# EC_meter.net
KiCad netlist of a schematic drawn in Altium Designer
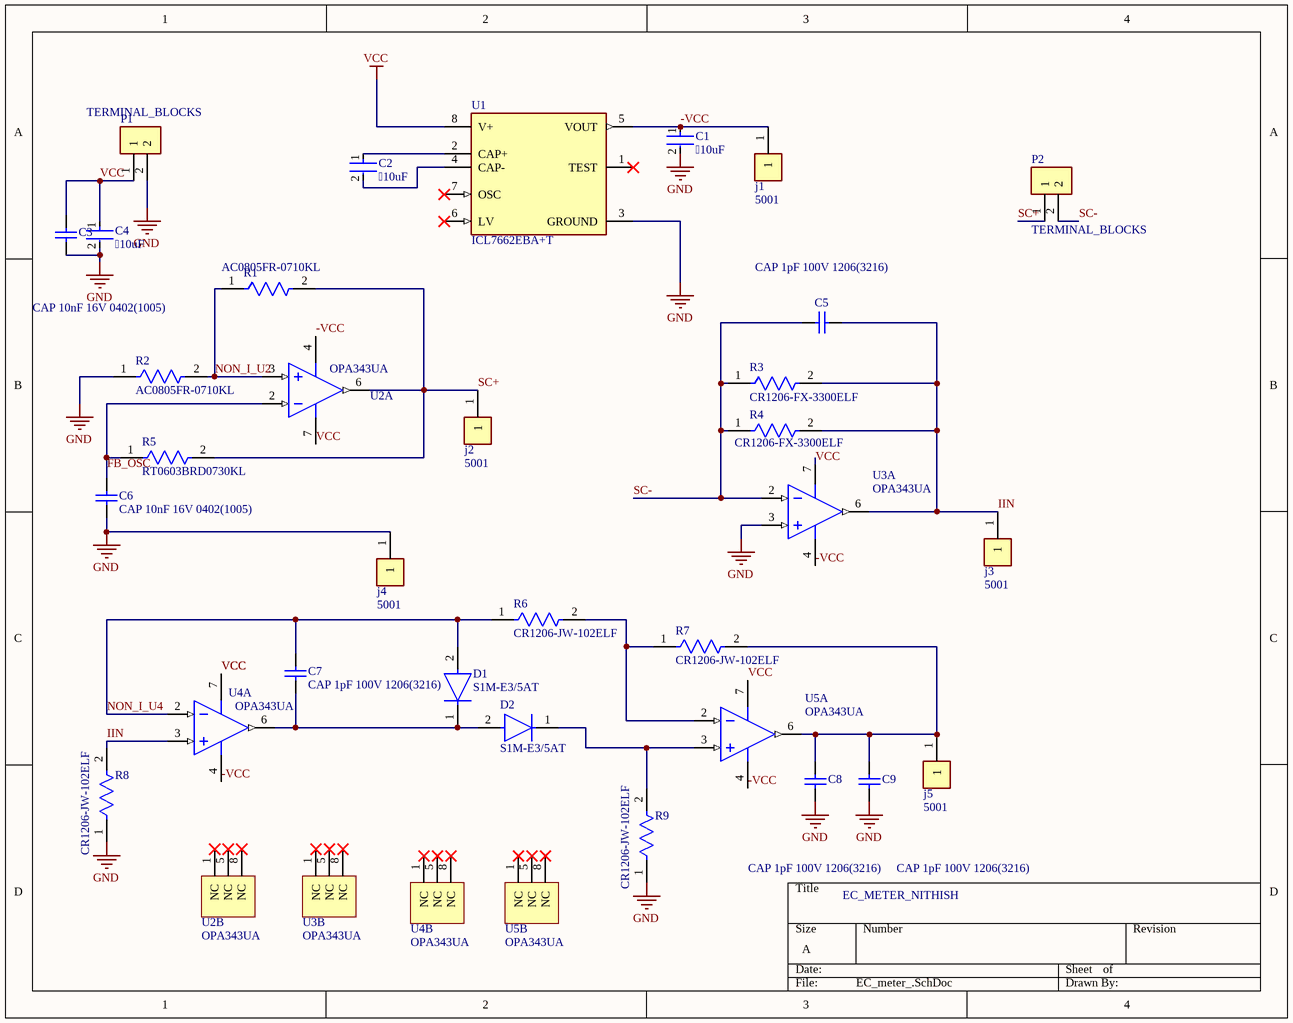
[diagram p0: EC_meter_.SchDoc]

(export (version "E")
  (design (tool "Eeschema 10.0.6"))
  (components
    (comp (ref "C1")
      (value "10uF")
      (footprint "FP-GRM31-0_2-MFG")
      (description "CAP CER 10UF 50V X5R 1206")
      (fields
        (field (name "OCTOPART") "https://octopart.com/grm31cr61h106ka12l-murata-18903335")
        (field (name "TOLERANCE") "10%")
      )
      (libsource (lib "Altium Content Vault") (part "11868f565c42a9108669ba33697ecf6"))
    )
    (comp (ref "C2")
      (value "10uF")
      (footprint "FP-GRM31-0_2-MFG")
      (description "CAP CER 10UF 50V X5R 1206")
      (fields
        (field (name "OCTOPART") "https://octopart.com/grm31cr61h106ka12l-murata-18903335")
        (field (name "TOLERANCE") "10%")
      )
      (libsource (lib "Altium Content Vault") (part "11868f565c42a9108669ba33697ecf6"))
    )
    (comp (ref "C3")
      (value "CAP 10nF 16V 0402(1005)")
      (footprint "CAPC0402(1005)60_M")
      (description "CAP 10nF 16V -20% to +80% 0402 (1005 Metric) Thickness 0.6mm SMD")
      (fields (field (name "TOLERANCE") "-20% to +80%"))
      (libsource (lib "Altium Content Vault") (part "CAP"))
    )
    (comp (ref "C4")
      (value "10uF")
      (footprint "FP-GRM31-0_2-MFG")
      (description "CAP CER 10UF 50V X5R 1206")
      (fields
        (field (name "OCTOPART") "https://octopart.com/grm31cr61h106ka12l-murata-18903335")
        (field (name "TOLERANCE") "10%")
      )
      (libsource (lib "Altium Content Vault") (part "11868f565c42a9108669ba33697ecf6"))
    )
    (comp (ref "C5")
      (value "CAP 1pF 100V 1206(3216)")
      (footprint "CAPC1206(3216)170_N")
      (description "CAP 1pF 100V ±0.25pF 1206 (3216 Metric) Thickness 1.7mm SMD")
      (fields (field (name "TOLERANCE") "Â±0.25pF"))
      (libsource (lib "Altium Content Vault") (part "CAP"))
    )
    (comp (ref "C6")
      (value "CAP 10nF 16V 0402(1005)")
      (footprint "CAPC0402(1005)60_M")
      (description "CAP 10nF 16V -20% to +80% 0402 (1005 Metric) Thickness 0.6mm SMD")
      (fields (field (name "TOLERANCE") "-20% to +80%"))
      (libsource (lib "Altium Content Vault") (part "CAP"))
    )
    (comp (ref "C7")
      (value "CAP 1pF 100V 1206(3216)")
      (footprint "CAPC1206(3216)170_N")
      (description "CAP 1pF 100V ±0.25pF 1206 (3216 Metric) Thickness 1.7mm SMD")
      (fields (field (name "TOLERANCE") "Â±0.25pF"))
      (libsource (lib "Altium Content Vault") (part "CAP"))
    )
    (comp (ref "C8")
      (value "CAP 1pF 100V 1206(3216)")
      (footprint "CAPC1206(3216)170_N")
      (description "CAP 1pF 100V ±0.25pF 1206 (3216 Metric) Thickness 1.7mm SMD")
      (fields (field (name "TOLERANCE") "Â±0.25pF"))
      (libsource (lib "Altium Content Vault") (part "CAP"))
    )
    (comp (ref "C9")
      (value "CAP 1pF 100V 1206(3216)")
      (footprint "CAPC1206(3216)170_N")
      (description "CAP 1pF 100V ±0.25pF 1206 (3216 Metric) Thickness 1.7mm SMD")
      (fields (field (name "TOLERANCE") "Â±0.25pF"))
      (libsource (lib "Altium Content Vault") (part "CAP"))
    )
    (comp (ref "D1")
      (value "S1M-E3/5AT")
      (footprint "FP-95400-MFG")
      (description "DIODE GEN PURP 1KV 1A DO214AC")
      (fields
        (field (name "OCTOPART") "https://octopart.com/s1m-e3%2F5at-vishay-42334588")
        (field (name "MANUFACTURER") "Vishay")
      )
      (libsource (lib "Altium Content Vault") (part "d7152d700b627762746794eb795d46e"))
    )
    (comp (ref "D2")
      (value "S1M-E3/5AT")
      (footprint "FP-95400-MFG")
      (description "DIODE GEN PURP 1KV 1A DO214AC")
      (fields
        (field (name "OCTOPART") "https://octopart.com/s1m-e3%2F5at-vishay-42334588")
        (field (name "MANUFACTURER") "Vishay")
      )
      (libsource (lib "Altium Content Vault") (part "d7152d700b627762746794eb795d46e"))
    )
    (comp (ref "j1")
      (value "5001")
      (footprint "FP-5001-MFG")
      (description "PC TEST POINT MINIATURE BLACK")
      (libsource (lib "Altium Content Vault") (part "1e4615820a309e3ce90f9e6d957b7fa"))
    )
    (comp (ref "j2")
      (value "5001")
      (footprint "FP-5001-MFG")
      (description "PC TEST POINT MINIATURE BLACK")
      (libsource (lib "Altium Content Vault") (part "1e4615820a309e3ce90f9e6d957b7fa"))
    )
    (comp (ref "j3")
      (value "5001")
      (footprint "FP-5001-MFG")
      (description "PC TEST POINT MINIATURE BLACK")
      (libsource (lib "Altium Content Vault") (part "1e4615820a309e3ce90f9e6d957b7fa"))
    )
    (comp (ref "j4")
      (value "5001")
      (footprint "FP-5001-MFG")
      (description "PC TEST POINT MINIATURE BLACK")
      (libsource (lib "Altium Content Vault") (part "1e4615820a309e3ce90f9e6d957b7fa"))
    )
    (comp (ref "j5")
      (value "5001")
      (footprint "FP-5001-MFG")
      (description "PC TEST POINT MINIATURE BLACK")
      (libsource (lib "Altium Content Vault") (part "1e4615820a309e3ce90f9e6d957b7fa"))
    )
    (comp (ref "P1")
      (value "TERMINAL_BLOCKS")
      (footprint "PCBComponent_1 - duplicate")
      (libsource (lib "EC_meter") (part "TERMINAL_BLOCKS"))
    )
    (comp (ref "P2")
      (value "TERMINAL_BLOCKS")
      (footprint "PCBComponent_1 - duplicate")
      (libsource (lib "EC_meter") (part "TERMINAL_BLOCKS"))
    )
    (comp (ref "R1")
      (value "AC0805FR-0710KL")
      (footprint "FP-AC0805-MFG")
      (description "RES SMD 10K OHM 1% 1/8W 0805")
      (fields
        (field (name "OCTOPART") "https://octopart.com/ac0805fr-0710kl-yageo-21711112")
        (field (name "MANUFACTURER") "Yageo")
      )
      (libsource (lib "Altium Content Vault") (part "1029c3af85768c4190bb7ad29bc67b5"))
    )
    (comp (ref "R2")
      (value "AC0805FR-0710KL")
      (footprint "FP-AC0805-MFG")
      (description "RES SMD 10K OHM 1% 1/8W 0805")
      (fields
        (field (name "OCTOPART") "https://octopart.com/ac0805fr-0710kl-yageo-21711112")
        (field (name "MANUFACTURER") "Yageo")
      )
      (libsource (lib "Altium Content Vault") (part "1029c3af85768c4190bb7ad29bc67b5"))
    )
    (comp (ref "R3")
      (value "CR1206-FX-3300ELF")
      (footprint "FP-CR1206-MFG")
      (description "Thick Film Chip Resistors 1206 330Ω 0.25W 1% 100ppm/°C")
      (fields (field (name "TOLERANCE") "1%"))
      (libsource (lib "Altium Content Vault") (part "1029c3af85768c4190bb7ad29bc67b5"))
    )
    (comp (ref "R4")
      (value "CR1206-FX-3300ELF")
      (footprint "FP-CR1206-MFG")
      (description "Thick Film Chip Resistors 1206 330Ω 0.25W 1% 100ppm/°C")
      (fields (field (name "TOLERANCE") "1%"))
      (libsource (lib "Altium Content Vault") (part "1029c3af85768c4190bb7ad29bc67b5"))
    )
    (comp (ref "R5")
      (value "RT0603BRD0730KL")
      (footprint "FP-RT0603-0_55-MFG")
      (fields (field (name "TOLERANCE") "0.1%"))
      (libsource (lib "Altium Content Vault") (part "1029c3af85768c4190bb7ad29bc67b5"))
    )
    (comp (ref "R6")
      (value "CR1206-JW-102ELF")
      (footprint "FP-CR1206-IPC_C")
      (description "Thick Film Chip Resistors 1206 1kΩ 0.25W 5% 200ppm/°C")
      (fields (field (name "TOLERANCE") "5%"))
      (libsource (lib "Altium Content Vault") (part "1029c3af85768c4190bb7ad29bc67b5"))
    )
    (comp (ref "R7")
      (value "CR1206-JW-102ELF")
      (footprint "FP-CR1206-IPC_C")
      (description "Thick Film Chip Resistors 1206 1kΩ 0.25W 5% 200ppm/°C")
      (fields (field (name "TOLERANCE") "5%"))
      (libsource (lib "Altium Content Vault") (part "1029c3af85768c4190bb7ad29bc67b5"))
    )
    (comp (ref "R8")
      (value "CR1206-JW-102ELF")
      (footprint "FP-CR1206-IPC_C")
      (description "Thick Film Chip Resistors 1206 1kΩ 0.25W 5% 200ppm/°C")
      (fields (field (name "TOLERANCE") "5%"))
      (libsource (lib "Altium Content Vault") (part "1029c3af85768c4190bb7ad29bc67b5"))
    )
    (comp (ref "R9")
      (value "CR1206-JW-102ELF")
      (footprint "FP-CR1206-IPC_C")
      (description "Thick Film Chip Resistors 1206 1kΩ 0.25W 5% 200ppm/°C")
      (fields (field (name "TOLERANCE") "5%"))
      (libsource (lib "Altium Content Vault") (part "1029c3af85768c4190bb7ad29bc67b5"))
    )
    (comp (ref "U1")
      (value "ICL7662EBA+T")
      (footprint "FP-S8-4-MFG")
      (description "IC REG CHARGE PUMP INV 8SOIC")
      (fields
        (field (name "OCTOPART") "https://octopart.com/icl7662eba%2Bt-maxim+integrated-39621878")
        (field (name "MANUFACTURER") "Maxim")
      )
      (libsource (lib "Altium Content Vault") (part "7c31683469e3d05514c0af981b8d864"))
    )
    (comp (ref "U2")
      (value "OPA343UA")
      (footprint "D0008A_M")
      (fields (field (name "MANUFACTURER") "Texas Instruments"))
      (libsource (lib "") (part "TI-OPA-8_1_1"))
    )
    (comp (ref "U3")
      (value "OPA343UA")
      (footprint "D0008A_M")
      (fields (field (name "MANUFACTURER") "Texas Instruments"))
      (libsource (lib "Altium Content Vault") (part "TI-OPA-8_1"))
    )
    (comp (ref "U4")
      (value "OPA343UA")
      (footprint "D0008A_M")
      (fields (field (name "MANUFACTURER") "Texas Instruments"))
      (libsource (lib "Altium Content Vault") (part "TI-OPA-8_1"))
    )
    (comp (ref "U5")
      (value "OPA343UA")
      (footprint "D0008A_M")
      (fields (field (name "MANUFACTURER") "Texas Instruments"))
      (libsource (lib "") (part "TI-OPA-8_1_1"))
    )
  )
  (nets
    (net (code "1") (name "/-VCC") (class "Default")
      (node (ref "C1") (pin "1") (pinfunction "1_1") (pintype "passive"))
      (node (ref "U1") (pin "5") (pinfunction "VOUT_5") (pintype "output"))
      (node (ref "U2") (pin "4") (pinfunction "V-_4") (pintype "power_in"))
      (node (ref "U3") (pin "4") (pinfunction "V-_4") (pintype "power_in"))
      (node (ref "U4") (pin "4") (pinfunction "V-_4") (pintype "power_in"))
      (node (ref "U5") (pin "4") (pinfunction "V-_4") (pintype "power_in"))
      (node (ref "j1") (pin "1") (pinfunction "1_1") (pintype "passive"))
    )
    (net (code "2") (name "/FB_OSC") (class "Default")
      (node (ref "C6") (pin "2") (pinfunction "2_2") (pintype "passive"))
      (node (ref "R5") (pin "1") (pinfunction "1_1") (pintype "passive"))
      (node (ref "U2") (pin "2") (pinfunction "IN-_2") (pintype "input"))
    )
    (net (code "3") (name "/IIN") (class "Default")
      (node (ref "C5") (pin "1") (pinfunction "1_1") (pintype "passive"))
      (node (ref "R3") (pin "2") (pinfunction "2_2") (pintype "passive"))
      (node (ref "R4") (pin "2") (pinfunction "2_2") (pintype "passive"))
      (node (ref "R8") (pin "2") (pinfunction "2_2") (pintype "passive"))
      (node (ref "U3") (pin "6") (pinfunction "OUT_6") (pintype "output"))
      (node (ref "U4") (pin "3") (pinfunction "IN+_3") (pintype "input"))
      (node (ref "j3") (pin "1") (pinfunction "1_1") (pintype "passive"))
    )
    (net (code "4") (name "/NON_I_U2") (class "Default")
      (node (ref "R1") (pin "1") (pinfunction "1_1") (pintype "passive"))
      (node (ref "R2") (pin "2") (pinfunction "2_2") (pintype "passive"))
      (node (ref "U2") (pin "3") (pinfunction "IN+_3") (pintype "input"))
    )
    (net (code "5") (name "/NON_I_U4") (class "Default")
      (node (ref "C7") (pin "2") (pinfunction "2_2") (pintype "passive"))
      (node (ref "D1") (pin "2") (pinfunction "A_2") (pintype "passive"))
      (node (ref "R6") (pin "1") (pinfunction "1_1") (pintype "passive"))
      (node (ref "U4") (pin "2") (pinfunction "IN-_2") (pintype "input"))
    )
    (net (code "6") (name "/SC+") (class "Default")
      (node (ref "P2") (pin "1") (pinfunction "1_1") (pintype "passive"))
      (node (ref "R1") (pin "2") (pinfunction "2_2") (pintype "passive"))
      (node (ref "R5") (pin "2") (pinfunction "2_2") (pintype "passive"))
      (node (ref "U2") (pin "6") (pinfunction "OUT_6") (pintype "output"))
      (node (ref "j2") (pin "1") (pinfunction "1_1") (pintype "passive"))
    )
    (net (code "7") (name "/SC-") (class "Default")
      (node (ref "C5") (pin "2") (pinfunction "2_2") (pintype "passive"))
      (node (ref "P2") (pin "2") (pinfunction "2_2") (pintype "passive"))
      (node (ref "R3") (pin "1") (pinfunction "1_1") (pintype "passive"))
      (node (ref "R4") (pin "1") (pinfunction "1_1") (pintype "passive"))
      (node (ref "U3") (pin "2") (pinfunction "IN-_2") (pintype "input"))
    )
    (net (code "8") (name "GND") (class "Default")
      (node (ref "C1") (pin "2") (pinfunction "2_2") (pintype "passive"))
      (node (ref "C3") (pin "1") (pinfunction "1_1") (pintype "passive"))
      (node (ref "C4") (pin "2") (pinfunction "2_2") (pintype "passive"))
      (node (ref "C6") (pin "1") (pinfunction "1_1") (pintype "passive"))
      (node (ref "C8") (pin "1") (pinfunction "1_1") (pintype "passive"))
      (node (ref "C9") (pin "1") (pinfunction "1_1") (pintype "passive"))
      (node (ref "P1") (pin "2") (pinfunction "2_2") (pintype "passive"))
      (node (ref "R2") (pin "1") (pinfunction "1_1") (pintype "passive"))
      (node (ref "R8") (pin "1") (pinfunction "1_1") (pintype "passive"))
      (node (ref "R9") (pin "1") (pinfunction "1_1") (pintype "passive"))
      (node (ref "U1") (pin "3") (pinfunction "GROUND_3") (pintype "power_in"))
      (node (ref "U3") (pin "3") (pinfunction "IN+_3") (pintype "input"))
      (node (ref "j4") (pin "1") (pinfunction "1_1") (pintype "passive"))
    )
    (net (code "9") (name "Net-(D1-C)") (class "Default")
      (node (ref "C7") (pin "1") (pinfunction "1_1") (pintype "passive"))
      (node (ref "D1") (pin "1") (pinfunction "C_1") (pintype "passive"))
      (node (ref "D2") (pin "2") (pinfunction "A_2") (pintype "passive"))
      (node (ref "U4") (pin "6") (pinfunction "OUT_6") (pintype "output"))
    )
    (net (code "10") (name "Net-(D2-C)") (class "Default")
      (node (ref "D2") (pin "1") (pinfunction "C_1") (pintype "passive"))
      (node (ref "R9") (pin "2") (pinfunction "2_2") (pintype "passive"))
      (node (ref "U5") (pin "3") (pinfunction "IN+_3") (pintype "input"))
    )
    (net (code "11") (name "Net-(U1-CAP+)") (class "Default")
      (node (ref "C2") (pin "1") (pinfunction "1_1") (pintype "passive"))
      (node (ref "U1") (pin "2") (pinfunction "CAP+_2") (pintype "power_in"))
    )
    (net (code "12") (name "Net-(U1-CAP-)") (class "Default")
      (node (ref "C2") (pin "2") (pinfunction "2_2") (pintype "passive"))
      (node (ref "U1") (pin "4") (pinfunction "CAP-_4") (pintype "power_in"))
    )
    (net (code "13") (name "Net-(U5A-IN-)") (class "Default")
      (node (ref "R6") (pin "2") (pinfunction "2_2") (pintype "passive"))
      (node (ref "R7") (pin "1") (pinfunction "1_1") (pintype "passive"))
      (node (ref "U5") (pin "2") (pinfunction "IN-_2") (pintype "input"))
    )
    (net (code "14") (name "Net-(U5A-OUT)") (class "Default")
      (node (ref "C8") (pin "2") (pinfunction "2_2") (pintype "passive"))
      (node (ref "C9") (pin "2") (pinfunction "2_2") (pintype "passive"))
      (node (ref "R7") (pin "2") (pinfunction "2_2") (pintype "passive"))
      (node (ref "U5") (pin "6") (pinfunction "OUT_6") (pintype "output"))
      (node (ref "j5") (pin "1") (pinfunction "1_1") (pintype "passive"))
    )
    (net (code "15") (name "VCC") (class "Default")
      (node (ref "C3") (pin "2") (pinfunction "2_2") (pintype "passive"))
      (node (ref "C4") (pin "1") (pinfunction "1_1") (pintype "passive"))
      (node (ref "P1") (pin "1") (pinfunction "1_1") (pintype "passive"))
      (node (ref "U1") (pin "8") (pinfunction "V+_8") (pintype "power_in"))
      (node (ref "U2") (pin "7") (pinfunction "V+_7") (pintype "power_in"))
      (node (ref "U3") (pin "7") (pinfunction "V+_7") (pintype "power_in"))
      (node (ref "U4") (pin "7") (pinfunction "V+_7") (pintype "power_in"))
      (node (ref "U5") (pin "7") (pinfunction "V+_7") (pintype "power_in"))
    )
    (net (code "16") (name "unconnected-(U1-LV-Pad6)") (class "Default")
      (node (ref "U1") (pin "6") (pinfunction "LV_6") (pintype "input+no_connect"))
    )
    (net (code "17") (name "unconnected-(U1-OSC-Pad7)") (class "Default")
      (node (ref "U1") (pin "7") (pinfunction "OSC_7") (pintype "input+no_connect"))
    )
    (net (code "18") (name "unconnected-(U1-TEST-Pad1)") (class "Default")
      (node (ref "U1") (pin "1") (pinfunction "TEST_1") (pintype "passive+no_connect"))
    )
    (net (code "19") (name "unconnected-(U2B-NC-Pad1)") (class "Default")
      (node (ref "U2") (pin "1") (pinfunction "NC_1") (pintype "passive+no_connect"))
    )
    (net (code "20") (name "unconnected-(U2B-NC-Pad5)") (class "Default")
      (node (ref "U2") (pin "5") (pinfunction "NC_5") (pintype "passive+no_connect"))
    )
    (net (code "21") (name "unconnected-(U2B-NC-Pad8)") (class "Default")
      (node (ref "U2") (pin "8") (pinfunction "NC_8") (pintype "passive+no_connect"))
    )
    (net (code "22") (name "unconnected-(U3B-NC-Pad1)") (class "Default")
      (node (ref "U3") (pin "1") (pinfunction "NC_1") (pintype "passive+no_connect"))
    )
    (net (code "23") (name "unconnected-(U3B-NC-Pad5)") (class "Default")
      (node (ref "U3") (pin "5") (pinfunction "NC_5") (pintype "passive+no_connect"))
    )
    (net (code "24") (name "unconnected-(U3B-NC-Pad8)") (class "Default")
      (node (ref "U3") (pin "8") (pinfunction "NC_8") (pintype "passive+no_connect"))
    )
    (net (code "25") (name "unconnected-(U4B-NC-Pad1)") (class "Default")
      (node (ref "U4") (pin "1") (pinfunction "NC_1") (pintype "passive+no_connect"))
    )
    (net (code "26") (name "unconnected-(U4B-NC-Pad5)") (class "Default")
      (node (ref "U4") (pin "5") (pinfunction "NC_5") (pintype "passive+no_connect"))
    )
    (net (code "27") (name "unconnected-(U4B-NC-Pad8)") (class "Default")
      (node (ref "U4") (pin "8") (pinfunction "NC_8") (pintype "passive+no_connect"))
    )
    (net (code "28") (name "unconnected-(U5B-NC-Pad1)") (class "Default")
      (node (ref "U5") (pin "1") (pinfunction "NC_1") (pintype "passive+no_connect"))
    )
    (net (code "29") (name "unconnected-(U5B-NC-Pad5)") (class "Default")
      (node (ref "U5") (pin "5") (pinfunction "NC_5") (pintype "passive+no_connect"))
    )
    (net (code "30") (name "unconnected-(U5B-NC-Pad8)") (class "Default")
      (node (ref "U5") (pin "8") (pinfunction "NC_8") (pintype "passive+no_connect"))
    )
  )
)
